# CaniqueMK2-rev4.net
KiCad netlist of a schematic drawn in EAGLE
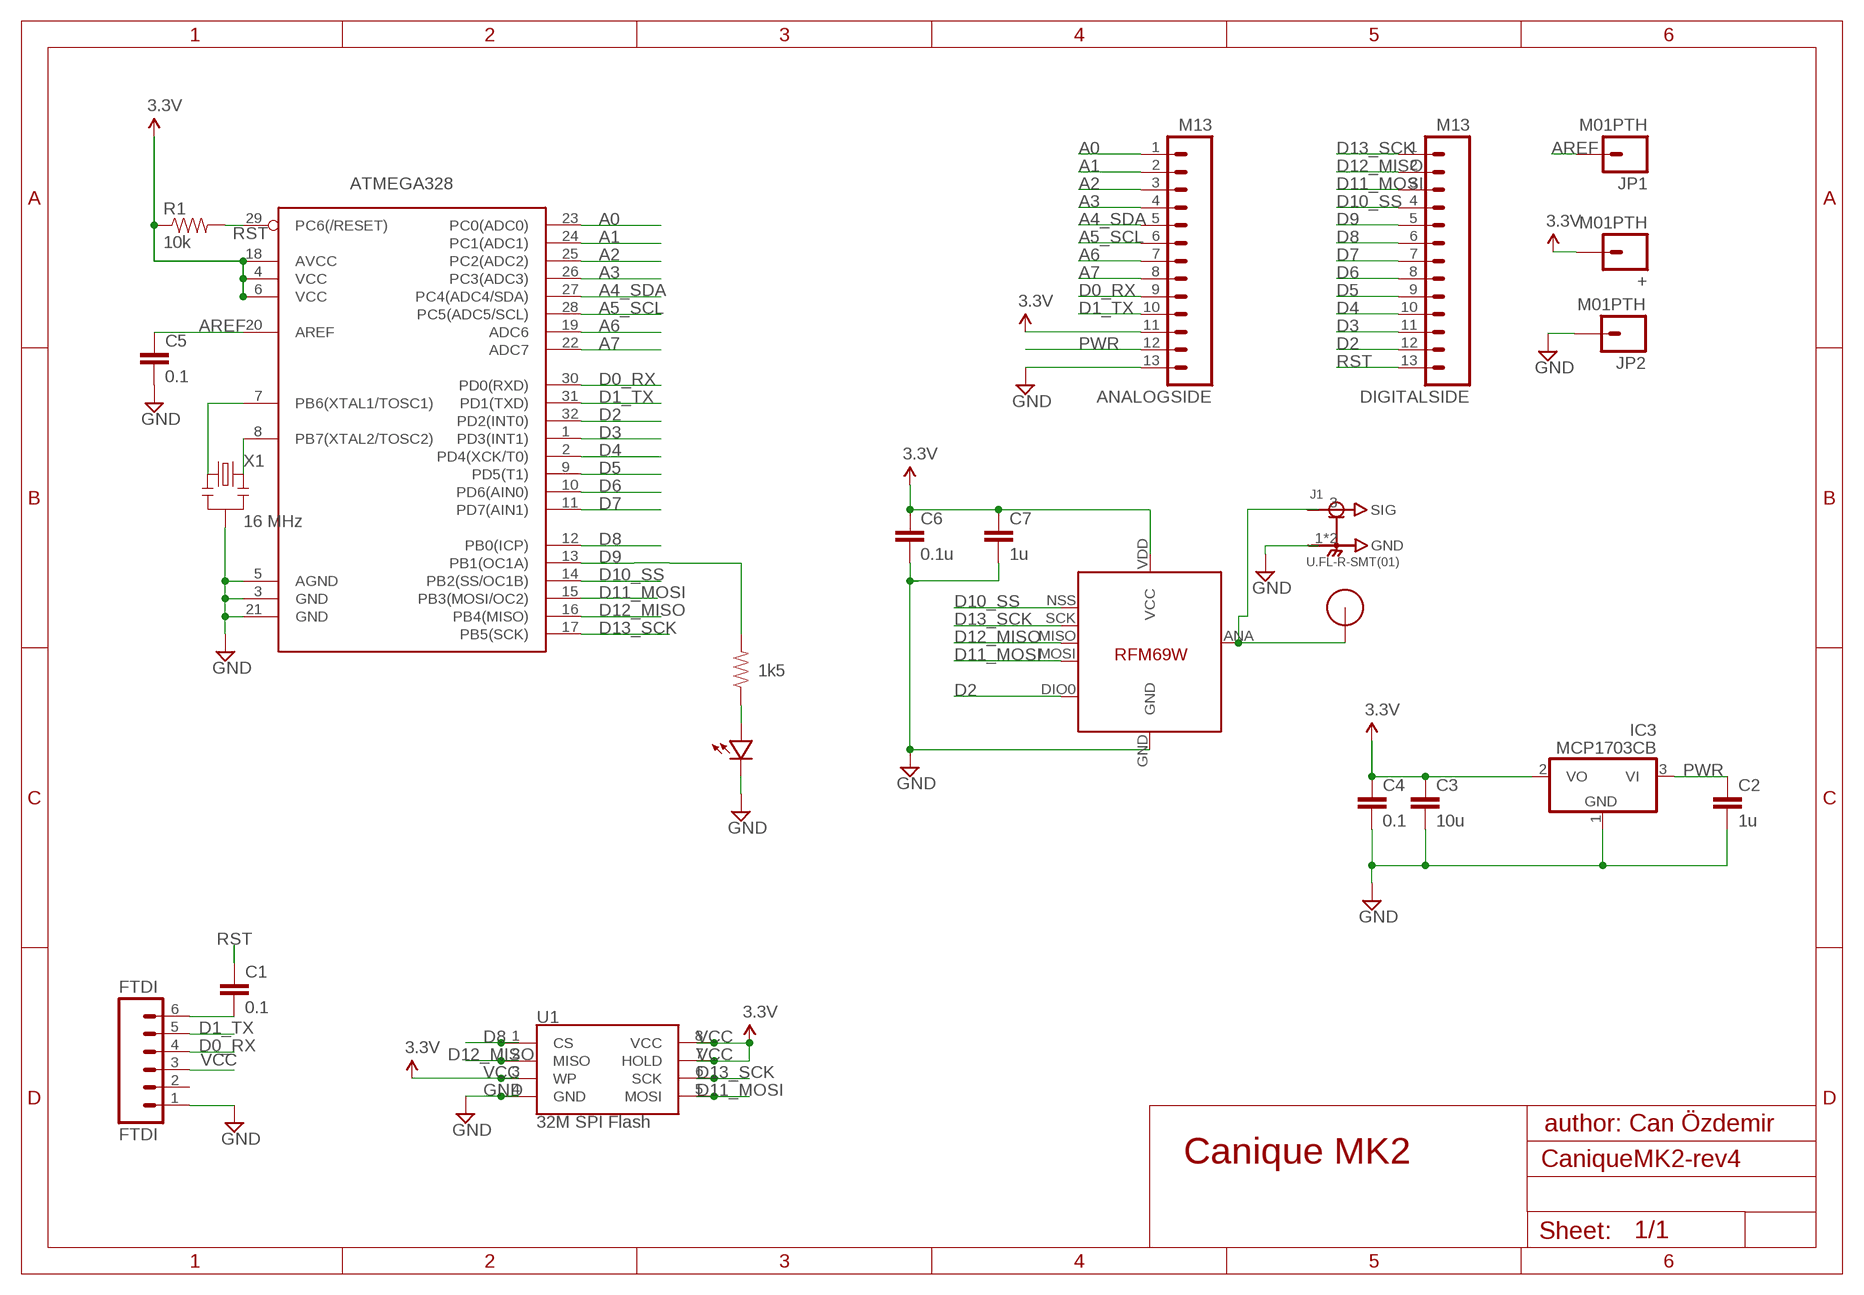
[diagram p0: schematic, sheet 1]

(export (version "E")
  (design (tool "Eeschema 10.0.6"))
  (components
    (comp (ref "+")
      (value "M01PTH")
      (footprint "eagle-import:1X01")
      (libsource (lib "eagle-import") (part "M01PTH"))
    )
    (comp (ref "ANALOGSIDE")
      (value "M13")
      (footprint "eagle-import:1X13")
      (libsource (lib "eagle-import") (part "M13"))
    )
    (comp (ref "ATMEGA328")
      (value "ATMega-328")
      (footprint "eagle-import:TQFP32-08")
      (libsource (lib "eagle-import") (part "ATMEGA168/328TQFP32"))
    )
    (comp (ref "C1")
      (value "0.1")
      (footprint "eagle-import:0603-CAP")
      (libsource (lib "eagle-import") (part "CAP0603-CAP"))
    )
    (comp (ref "C2")
      (value "1u")
      (footprint "eagle-import:0603-CAP")
      (libsource (lib "eagle-import") (part "CAP0603-CAP"))
    )
    (comp (ref "C3")
      (value "10u")
      (footprint "eagle-import:0805-CAP")
      (libsource (lib "eagle-import") (part "CAP0805-CAP"))
    )
    (comp (ref "C4")
      (value "0.1")
      (footprint "eagle-import:0603-CAP")
      (libsource (lib "eagle-import") (part "CAP0603-CAP"))
    )
    (comp (ref "C5")
      (value "0.1")
      (footprint "eagle-import:0603-CAP")
      (libsource (lib "eagle-import") (part "CAP0603-CAP"))
    )
    (comp (ref "C6")
      (value "0.1u")
      (footprint "eagle-import:0603-CAP")
      (libsource (lib "eagle-import") (part "CAP0603-CAP"))
    )
    (comp (ref "C7")
      (value "1u")
      (footprint "eagle-import:0603-CAP")
      (libsource (lib "eagle-import") (part "CAP0603-CAP"))
    )
    (comp (ref "DIGITALSIDE")
      (value "M13")
      (footprint "eagle-import:1X13")
      (libsource (lib "eagle-import") (part "M13"))
    )
    (comp (ref "FTDI")
      (value "FTDI")
      (footprint "eagle-import:1X06")
      (libsource (lib "eagle-import") (part "M06SIP"))
    )
    (comp (ref "IC3")
      (value "MCP1703CB")
      (footprint "eagle-import:SOT23")
      (libsource (lib "eagle-import") (part "MCP1703CB"))
    )
    (comp (ref "J1")
      (value "U.FL-R-SMT(01)")
      (footprint "eagle-import:HRS_U.FL-R-SMT(01)")
      (fields (field (name "MF") "Hirose"))
      (libsource (lib "eagle-import") (part "U.FL-R-SMT(01)"))
    )
    (comp (ref "JP1")
      (value "M01PTH")
      (footprint "eagle-import:1X01")
      (libsource (lib "eagle-import") (part "M01PTH"))
    )
    (comp (ref "JP2")
      (value "M01PTH")
      (footprint "eagle-import:1X01")
      (libsource (lib "eagle-import") (part "M01PTH"))
    )
    (comp (ref "R1")
      (value "10k")
      (footprint "eagle-import:0603-RES")
      (libsource (lib "eagle-import") (part "RESISTOR0603-RES"))
    )
    (comp (ref "R2")
      (value "1k5")
      (footprint "eagle-import:0603-RES")
      (libsource (lib "eagle-import") (part "RESISTOR0603-RES"))
    )
    (comp (ref "U$1")
      (value "RFM12B_ANTENNA")
      (footprint "eagle-import:RFM12B-ANTENNA")
      (libsource (lib "eagle-import") (part "RFM12B_ANTENNA"))
    )
    (comp (ref "U$2")
      (value "LED0603")
      (footprint "eagle-import:0603-LED")
      (libsource (lib "eagle-import") (part "LED0603"))
    )
    (comp (ref "U$5")
      (value "RFM69")
      (footprint "eagle-import:RFM69W-MINPADS")
      (libsource (lib "eagle-import") (part "RFM69"))
    )
    (comp (ref "U1")
      (value "32M SPI Flash")
      (footprint "eagle-import:SO08")
      (libsource (lib "eagle-import") (part "SPI_FLASH-X25XXSMD"))
    )
    (comp (ref "X1")
      (value "16 MHz")
      (footprint "eagle-import:RESONATOR-SMD")
      (libsource (lib "eagle-import") (part "RESONATORSMD"))
    )
  )
  (nets
    (net (code "1") (name "/A0") (class "Default")
      (node (ref "ANALOGSIDE") (pin "1") (pinfunction "1_1") (pintype "passive"))
      (node (ref "ATMEGA328") (pin "23") (pinfunction "PC0(ADC0)_23") (pintype "bidirectional"))
    )
    (net (code "2") (name "/A1") (class "Default")
      (node (ref "ANALOGSIDE") (pin "2") (pinfunction "2_2") (pintype "passive"))
      (node (ref "ATMEGA328") (pin "24") (pinfunction "PC1(ADC1)_24") (pintype "bidirectional"))
    )
    (net (code "3") (name "/A2") (class "Default")
      (node (ref "ANALOGSIDE") (pin "3") (pinfunction "3_3") (pintype "passive"))
      (node (ref "ATMEGA328") (pin "25") (pinfunction "PC2(ADC2)_25") (pintype "bidirectional"))
    )
    (net (code "4") (name "/A3") (class "Default")
      (node (ref "ANALOGSIDE") (pin "4") (pinfunction "4_4") (pintype "passive"))
      (node (ref "ATMEGA328") (pin "26") (pinfunction "PC3(ADC3)_26") (pintype "bidirectional"))
    )
    (net (code "5") (name "/A4_SDA") (class "Default")
      (node (ref "ANALOGSIDE") (pin "5") (pinfunction "5_5") (pintype "passive"))
      (node (ref "ATMEGA328") (pin "27") (pinfunction "PC4(ADC4/SDA)_27") (pintype "bidirectional"))
    )
    (net (code "6") (name "/A5_SCL") (class "Default")
      (node (ref "ANALOGSIDE") (pin "6") (pinfunction "6_6") (pintype "passive"))
      (node (ref "ATMEGA328") (pin "28") (pinfunction "PC5(ADC5/SCL)_28") (pintype "bidirectional"))
    )
    (net (code "7") (name "/A6") (class "Default")
      (node (ref "ANALOGSIDE") (pin "7") (pinfunction "7_7") (pintype "passive"))
      (node (ref "ATMEGA328") (pin "19") (pinfunction "ADC6_19") (pintype "bidirectional"))
    )
    (net (code "8") (name "/A7") (class "Default")
      (node (ref "ANALOGSIDE") (pin "8") (pinfunction "8_8") (pintype "passive"))
      (node (ref "ATMEGA328") (pin "22") (pinfunction "ADC7_22") (pintype "bidirectional"))
    )
    (net (code "9") (name "/AREF") (class "Default")
      (node (ref "ATMEGA328") (pin "20") (pinfunction "AREF_20") (pintype "bidirectional"))
      (node (ref "C5") (pin "1") (pinfunction "1_1") (pintype "passive"))
      (node (ref "JP1") (pin "1") (pinfunction "1_1") (pintype "passive"))
    )
    (net (code "10") (name "/D0_RX") (class "Default")
      (node (ref "ANALOGSIDE") (pin "9") (pinfunction "9_9") (pintype "passive"))
      (node (ref "ATMEGA328") (pin "30") (pinfunction "PD0(RXD)_30") (pintype "bidirectional"))
      (node (ref "FTDI") (pin "4") (pinfunction "4_4") (pintype "passive"))
    )
    (net (code "11") (name "/D1_TX") (class "Default")
      (node (ref "ANALOGSIDE") (pin "10") (pinfunction "10_10") (pintype "passive"))
      (node (ref "ATMEGA328") (pin "31") (pinfunction "PD1(TXD)_31") (pintype "bidirectional"))
      (node (ref "FTDI") (pin "5") (pinfunction "5_5") (pintype "passive"))
    )
    (net (code "12") (name "/D2") (class "Default")
      (node (ref "ATMEGA328") (pin "32") (pinfunction "PD2(INT0)_32") (pintype "bidirectional"))
      (node (ref "DIGITALSIDE") (pin "12") (pinfunction "12_12") (pintype "passive"))
      (node (ref "U$5") (pin "DIO0") (pinfunction "DIO0_DIO0") (pintype "open_collector"))
    )
    (net (code "13") (name "/D3") (class "Default")
      (node (ref "ATMEGA328") (pin "1") (pinfunction "PD3(INT1)_1") (pintype "bidirectional"))
      (node (ref "DIGITALSIDE") (pin "11") (pinfunction "11_11") (pintype "passive"))
    )
    (net (code "14") (name "/D4") (class "Default")
      (node (ref "ATMEGA328") (pin "2") (pinfunction "PD4(XCK/T0)_2") (pintype "bidirectional"))
      (node (ref "DIGITALSIDE") (pin "10") (pinfunction "10_10") (pintype "passive"))
    )
    (net (code "15") (name "/D5") (class "Default")
      (node (ref "ATMEGA328") (pin "9") (pinfunction "PD5(T1)_9") (pintype "bidirectional"))
      (node (ref "DIGITALSIDE") (pin "9") (pinfunction "9_9") (pintype "passive"))
    )
    (net (code "16") (name "/D6") (class "Default")
      (node (ref "ATMEGA328") (pin "10") (pinfunction "PD6(AIN0)_10") (pintype "bidirectional"))
      (node (ref "DIGITALSIDE") (pin "8") (pinfunction "8_8") (pintype "passive"))
    )
    (net (code "17") (name "/D7") (class "Default")
      (node (ref "ATMEGA328") (pin "11") (pinfunction "PD7(AIN1)_11") (pintype "bidirectional"))
      (node (ref "DIGITALSIDE") (pin "7") (pinfunction "7_7") (pintype "passive"))
    )
    (net (code "18") (name "/D8") (class "Default")
      (node (ref "ATMEGA328") (pin "12") (pinfunction "PB0(ICP)_12") (pintype "bidirectional"))
      (node (ref "DIGITALSIDE") (pin "6") (pinfunction "6_6") (pintype "passive"))
      (node (ref "U1") (pin "1") (pinfunction "CS_1") (pintype "bidirectional"))
    )
    (net (code "19") (name "/D9") (class "Default")
      (node (ref "ATMEGA328") (pin "13") (pinfunction "PB1(OC1A)_13") (pintype "bidirectional"))
      (node (ref "DIGITALSIDE") (pin "5") (pinfunction "5_5") (pintype "passive"))
      (node (ref "R2") (pin "2") (pinfunction "2_2") (pintype "passive"))
    )
    (net (code "20") (name "/D10_SS") (class "Default")
      (node (ref "ATMEGA328") (pin "14") (pinfunction "PB2(SS/OC1B)_14") (pintype "bidirectional"))
      (node (ref "DIGITALSIDE") (pin "4") (pinfunction "4_4") (pintype "passive"))
      (node (ref "U$5") (pin "NSS") (pinfunction "SEL_NSS") (pintype "input"))
    )
    (net (code "21") (name "/D11_MOSI") (class "Default")
      (node (ref "ATMEGA328") (pin "15") (pinfunction "PB3(MOSI/OC2)_15") (pintype "bidirectional"))
      (node (ref "DIGITALSIDE") (pin "3") (pinfunction "3_3") (pintype "passive"))
      (node (ref "U$5") (pin "MOSI") (pinfunction "MOSI_MOSI") (pintype "output"))
      (node (ref "U1") (pin "5") (pinfunction "MOSI_5") (pintype "bidirectional"))
    )
    (net (code "22") (name "/D12_MISO") (class "Default")
      (node (ref "ATMEGA328") (pin "16") (pinfunction "PB4(MISO)_16") (pintype "bidirectional"))
      (node (ref "DIGITALSIDE") (pin "2") (pinfunction "2_2") (pintype "passive"))
      (node (ref "U$5") (pin "MISO") (pinfunction "MISO_MISO") (pintype "input"))
      (node (ref "U1") (pin "2") (pinfunction "MISO_2") (pintype "bidirectional"))
    )
    (net (code "23") (name "/D13_SCK") (class "Default")
      (node (ref "ATMEGA328") (pin "17") (pinfunction "PB5(SCK)_17") (pintype "bidirectional"))
      (node (ref "DIGITALSIDE") (pin "1") (pinfunction "1_1") (pintype "passive"))
      (node (ref "U$5") (pin "SCK") (pinfunction "SCK_SCK") (pintype "input"))
      (node (ref "U1") (pin "6") (pinfunction "SCK_6") (pintype "bidirectional"))
    )
    (net (code "24") (name "/PWR") (class "Default")
      (node (ref "ANALOGSIDE") (pin "12") (pinfunction "12_12") (pintype "passive"))
      (node (ref "C2") (pin "1") (pinfunction "1_1") (pintype "passive"))
      (node (ref "IC3") (pin "3") (pinfunction "VI_3") (pintype "input"))
    )
    (net (code "25") (name "/RST") (class "Default")
      (node (ref "ATMEGA328") (pin "29") (pinfunction "PC6(/RESET)_29") (pintype "bidirectional"))
      (node (ref "C1") (pin "1") (pinfunction "1_1") (pintype "passive"))
      (node (ref "DIGITALSIDE") (pin "13") (pinfunction "13_13") (pintype "passive"))
      (node (ref "R1") (pin "2") (pinfunction "2_2") (pintype "passive"))
    )
    (net (code "26") (name "3.3V") (class "Default")
      (node (ref "+") (pin "1") (pinfunction "1_1") (pintype "passive"))
      (node (ref "ANALOGSIDE") (pin "11") (pinfunction "11_11") (pintype "passive"))
      (node (ref "ATMEGA328") (pin "18") (pinfunction "AVCC_18") (pintype "bidirectional"))
      (node (ref "ATMEGA328") (pin "4") (pinfunction "VCC_4") (pintype "bidirectional"))
      (node (ref "ATMEGA328") (pin "6") (pinfunction "VCC_6") (pintype "bidirectional"))
      (node (ref "C3") (pin "1") (pinfunction "1_1") (pintype "passive"))
      (node (ref "C4") (pin "1") (pinfunction "1_1") (pintype "passive"))
      (node (ref "C6") (pin "1") (pinfunction "1_1") (pintype "passive"))
      (node (ref "C7") (pin "1") (pinfunction "1_1") (pintype "passive"))
      (node (ref "FTDI") (pin "3") (pinfunction "3_3") (pintype "passive"))
      (node (ref "IC3") (pin "2") (pinfunction "VO_2") (pintype "passive"))
      (node (ref "R1") (pin "1") (pinfunction "1_1") (pintype "passive"))
      (node (ref "U$5") (pin "VDD") (pinfunction "VCC_VDD") (pintype "power_in"))
      (node (ref "U1") (pin "3") (pinfunction "WP_3") (pintype "bidirectional"))
      (node (ref "U1") (pin "7") (pinfunction "HOLD_7") (pintype "bidirectional"))
      (node (ref "U1") (pin "8") (pinfunction "VCC_8") (pintype "power_in"))
    )
    (net (code "27") (name "GND") (class "Default")
      (node (ref "ANALOGSIDE") (pin "13") (pinfunction "13_13") (pintype "passive"))
      (node (ref "ATMEGA328") (pin "21") (pinfunction "GND_21") (pintype "bidirectional"))
      (node (ref "ATMEGA328") (pin "3") (pinfunction "GND_3") (pintype "bidirectional"))
      (node (ref "ATMEGA328") (pin "5") (pinfunction "AGND_5") (pintype "bidirectional"))
      (node (ref "C2") (pin "2") (pinfunction "2_2") (pintype "passive"))
      (node (ref "C3") (pin "2") (pinfunction "2_2") (pintype "passive"))
      (node (ref "C4") (pin "2") (pinfunction "2_2") (pintype "passive"))
      (node (ref "C5") (pin "2") (pinfunction "2_2") (pintype "passive"))
      (node (ref "C6") (pin "2") (pinfunction "2_2") (pintype "passive"))
      (node (ref "C7") (pin "2") (pinfunction "2_2") (pintype "passive"))
      (node (ref "FTDI") (pin "1") (pinfunction "1_1") (pintype "passive"))
      (node (ref "IC3") (pin "1") (pinfunction "GND_1") (pintype "passive"))
      (node (ref "J1") (pin "1") (pinfunction "GND_1") (pintype "passive"))
      (node (ref "J1") (pin "2") (pinfunction "GND_2") (pintype "passive"))
      (node (ref "JP2") (pin "1") (pinfunction "1_1") (pintype "passive"))
      (node (ref "U$2") (pin "MINUS") (pinfunction "MINUS_MINUS") (pintype "passive"))
      (node (ref "U$5") (pin "GND") (pinfunction "GND_GND") (pintype "power_in"))
      (node (ref "U1") (pin "4") (pinfunction "GND_4") (pintype "power_in"))
      (node (ref "X1") (pin "2") (pinfunction "2_2") (pintype "passive"))
    )
    (net (code "28") (name "Net-(ATMEGA328-PB6(XTAL1{slash}TOSC1))") (class "Default")
      (node (ref "ATMEGA328") (pin "7") (pinfunction "PB6(XTAL1/TOSC1)_7") (pintype "bidirectional"))
      (node (ref "X1") (pin "1") (pinfunction "1_1") (pintype "passive"))
    )
    (net (code "29") (name "Net-(ATMEGA328-PB7(XTAL2{slash}TOSC2))") (class "Default")
      (node (ref "ATMEGA328") (pin "8") (pinfunction "PB7(XTAL2/TOSC2)_8") (pintype "bidirectional"))
      (node (ref "X1") (pin "3") (pinfunction "3_3") (pintype "passive"))
    )
    (net (code "30") (name "Net-(C1-Pad2)") (class "Default")
      (node (ref "C1") (pin "2") (pinfunction "2_2") (pintype "passive"))
      (node (ref "FTDI") (pin "6") (pinfunction "6_6") (pintype "passive"))
    )
    (net (code "31") (name "Net-(J1-SIG)") (class "Default")
      (node (ref "J1") (pin "3") (pinfunction "SIG_3") (pintype "passive"))
      (node (ref "U$1") (pin "P$1") (pinfunction "1_P$1") (pintype "bidirectional"))
      (node (ref "U$5") (pin "ANA") (pinfunction "ANT_ANA") (pintype "passive"))
    )
    (net (code "32") (name "Net-(R2-Pad1)") (class "Default")
      (node (ref "R2") (pin "1") (pinfunction "1_1") (pintype "passive"))
      (node (ref "U$2") (pin "PLUS") (pinfunction "PLUS_PLUS") (pintype "passive"))
    )
    (net (code "33") (name "unconnected-(FTDI-Pad2)") (class "Default")
      (node (ref "FTDI") (pin "2") (pinfunction "2_2") (pintype "passive"))
    )
  )
)
